# working.net
KiCad netlist of a schematic drawn in EAGLE
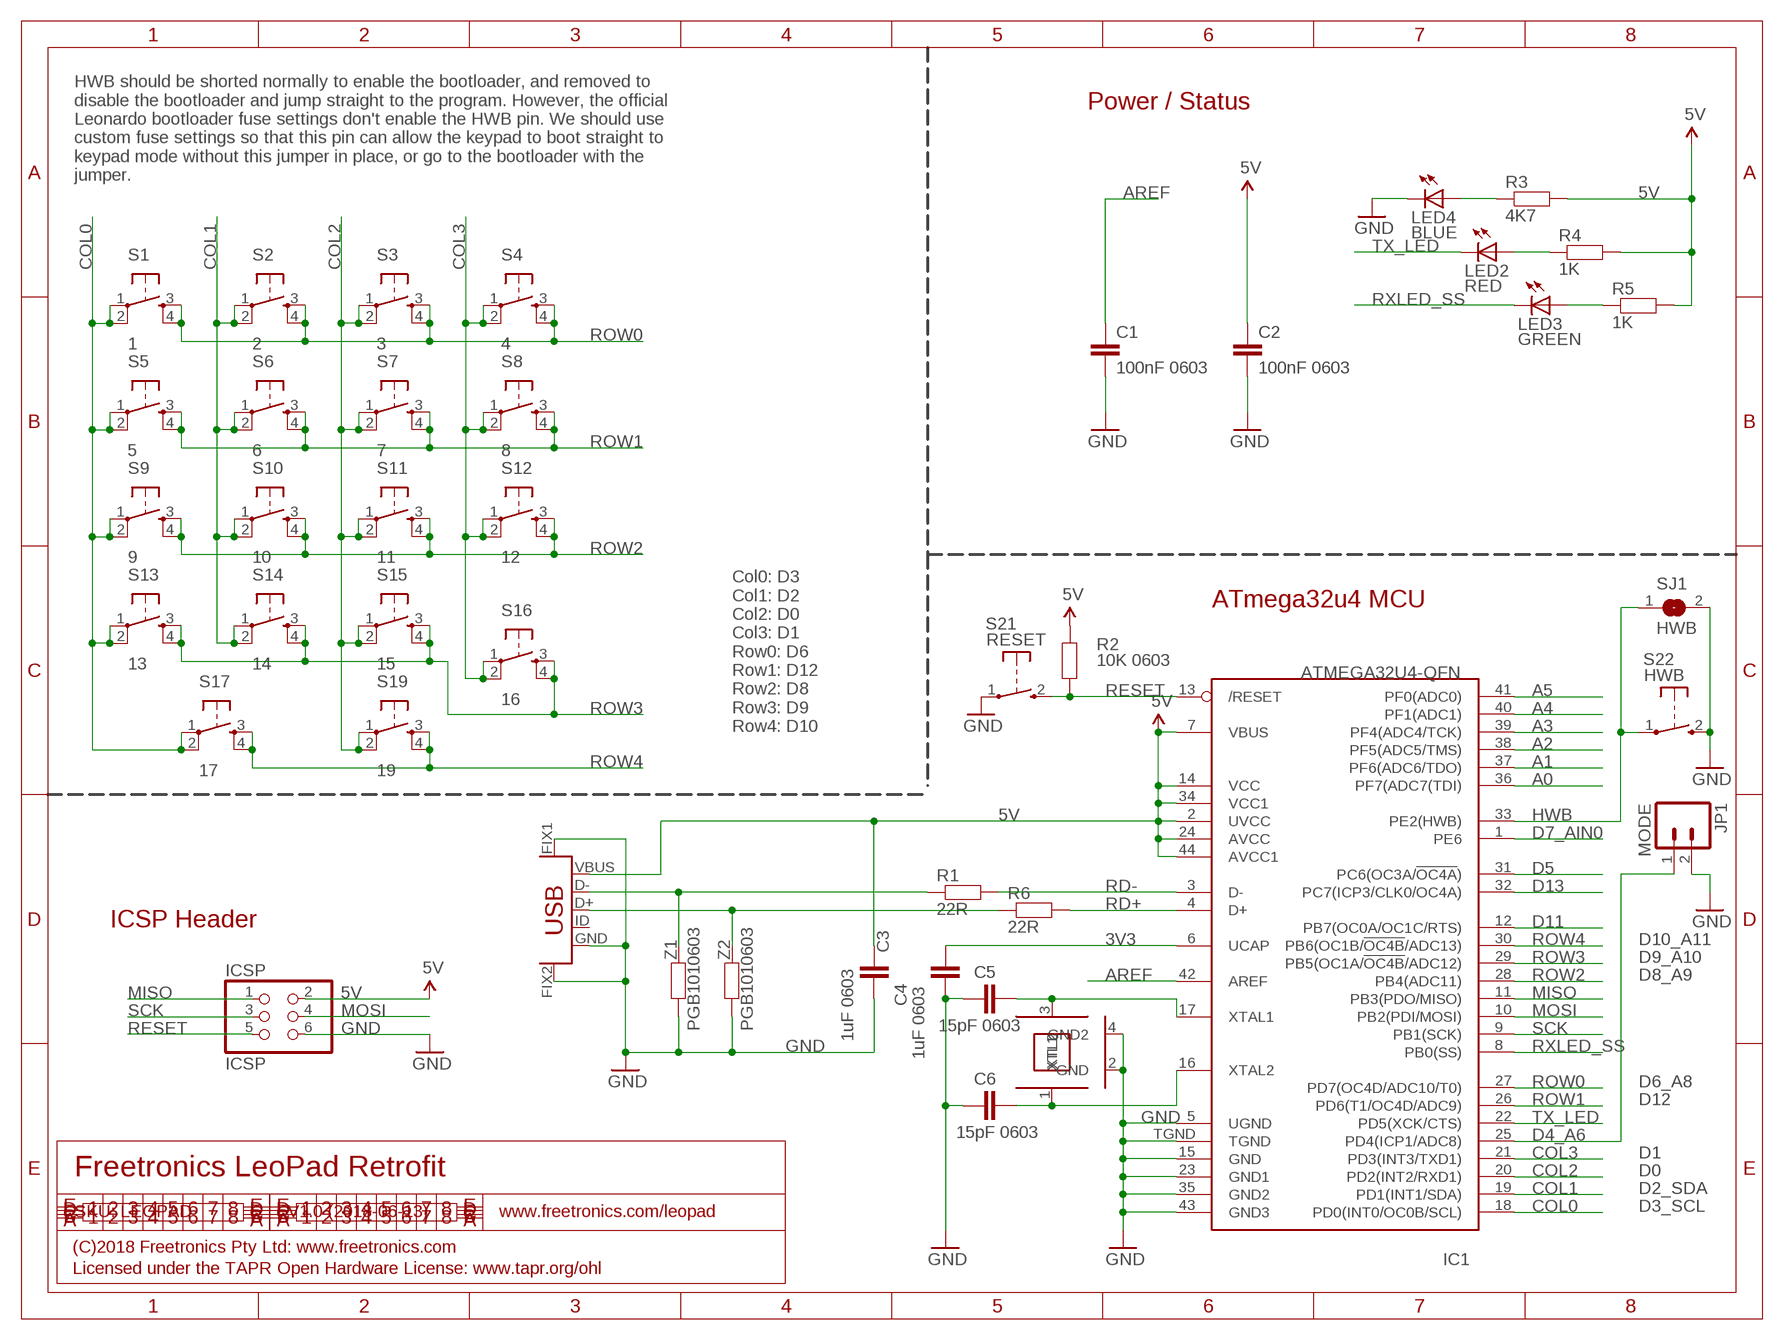
[diagram p0: schematic, sheet 1]

(export (version "E")
  (design (tool "Eeschema 10.0.6"))
  (components
    (comp (ref "C1")
      (value "100nF 0603")
      (footprint "eagle-import:0603")
      (libsource (lib "eagle-import") (part "CAP0603"))
    )
    (comp (ref "C2")
      (value "100nF 0603")
      (footprint "eagle-import:0603")
      (libsource (lib "eagle-import") (part "CAP0603"))
    )
    (comp (ref "C3")
      (value "1uF 0603")
      (footprint "eagle-import:0603")
      (libsource (lib "eagle-import") (part "CAP0603"))
    )
    (comp (ref "C4")
      (value "1uF 0603")
      (footprint "eagle-import:0603")
      (libsource (lib "eagle-import") (part "CAP0603"))
    )
    (comp (ref "C5")
      (value "15pF 0603")
      (footprint "eagle-import:0603")
      (libsource (lib "eagle-import") (part "CAP0603"))
    )
    (comp (ref "C6")
      (value "15pF 0603")
      (footprint "eagle-import:0603")
      (libsource (lib "eagle-import") (part "CAP0603"))
    )
    (comp (ref "IC1")
      (value "ATMEGA32U4-QFN")
      (footprint "eagle-import:QFN-44N")
      (libsource (lib "eagle-import") (part "ATMEGA32U4-QFN"))
    )
    (comp (ref "ICSP")
      (value "ICSP")
      (footprint "eagle-import:2X03")
      (libsource (lib "eagle-import") (part "PINHD-2X3"))
    )
    (comp (ref "JP1")
      (value "MODE")
      (footprint "eagle-import:1X02")
      (libsource (lib "eagle-import") (part "M02PTH"))
    )
    (comp (ref "LED2")
      (value "RED")
      (footprint "eagle-import:LED-0603")
      (libsource (lib "eagle-import") (part "LED0603"))
    )
    (comp (ref "LED3")
      (value "GREEN")
      (footprint "eagle-import:LED-0603")
      (libsource (lib "eagle-import") (part "LED0603"))
    )
    (comp (ref "LED4")
      (value "BLUE")
      (footprint "eagle-import:LED3MM")
      (libsource (lib "eagle-import") (part "LED3MM"))
    )
    (comp (ref "R1")
      (value "22R")
      (footprint "eagle-import:0603")
      (libsource (lib "eagle-import") (part "RESISTOR0603"))
    )
    (comp (ref "R2")
      (value "10K 0603")
      (footprint "eagle-import:0603")
      (libsource (lib "eagle-import") (part "freetronics-master-v1.1_RESISTOR0603"))
    )
    (comp (ref "R3")
      (value "4K7")
      (footprint "eagle-import:0603")
      (libsource (lib "eagle-import") (part "RESISTOR0603"))
    )
    (comp (ref "R4")
      (value "1K")
      (footprint "eagle-import:0603")
      (libsource (lib "eagle-import") (part "RESISTOR0603"))
    )
    (comp (ref "R5")
      (value "1K")
      (footprint "eagle-import:0603")
      (libsource (lib "eagle-import") (part "RESISTOR0603"))
    )
    (comp (ref "R6")
      (value "22R")
      (footprint "eagle-import:0603")
      (libsource (lib "eagle-import") (part "RESISTOR0603"))
    )
    (comp (ref "S1")
      (value "1")
      (footprint "eagle-import:TACTILE_SWITCH_SMD")
      (libsource (lib "eagle-import") (part "TAC_SWITCHSMD"))
    )
    (comp (ref "S2")
      (value "2")
      (footprint "eagle-import:TACTILE_SWITCH_SMD")
      (libsource (lib "eagle-import") (part "TAC_SWITCHSMD"))
    )
    (comp (ref "S3")
      (value "3")
      (footprint "eagle-import:TACTILE_SWITCH_SMD")
      (libsource (lib "eagle-import") (part "TAC_SWITCHSMD"))
    )
    (comp (ref "S4")
      (value "4")
      (footprint "eagle-import:TACTILE_SWITCH_SMD")
      (libsource (lib "eagle-import") (part "TAC_SWITCHSMD"))
    )
    (comp (ref "S5")
      (value "5")
      (footprint "eagle-import:TACTILE_SWITCH_SMD")
      (libsource (lib "eagle-import") (part "TAC_SWITCHSMD"))
    )
    (comp (ref "S6")
      (value "6")
      (footprint "eagle-import:TACTILE_SWITCH_SMD")
      (libsource (lib "eagle-import") (part "TAC_SWITCHSMD"))
    )
    (comp (ref "S7")
      (value "7")
      (footprint "eagle-import:TACTILE_SWITCH_SMD")
      (libsource (lib "eagle-import") (part "TAC_SWITCHSMD"))
    )
    (comp (ref "S8")
      (value "8")
      (footprint "eagle-import:TACTILE_SWITCH_SMD")
      (libsource (lib "eagle-import") (part "TAC_SWITCHSMD"))
    )
    (comp (ref "S9")
      (value "9")
      (footprint "eagle-import:TACTILE_SWITCH_SMD")
      (libsource (lib "eagle-import") (part "TAC_SWITCHSMD"))
    )
    (comp (ref "S10")
      (value "10")
      (footprint "eagle-import:TACTILE_SWITCH_SMD")
      (libsource (lib "eagle-import") (part "TAC_SWITCHSMD"))
    )
    (comp (ref "S11")
      (value "11")
      (footprint "eagle-import:TACTILE_SWITCH_SMD")
      (libsource (lib "eagle-import") (part "TAC_SWITCHSMD"))
    )
    (comp (ref "S12")
      (value "12")
      (footprint "eagle-import:TACTILE_SWITCH_SMD")
      (libsource (lib "eagle-import") (part "TAC_SWITCHSMD"))
    )
    (comp (ref "S13")
      (value "13")
      (footprint "eagle-import:TACTILE_SWITCH_SMD")
      (libsource (lib "eagle-import") (part "TAC_SWITCHSMD"))
    )
    (comp (ref "S14")
      (value "14")
      (footprint "eagle-import:TACTILE_SWITCH_SMD")
      (libsource (lib "eagle-import") (part "TAC_SWITCHSMD"))
    )
    (comp (ref "S15")
      (value "15")
      (footprint "eagle-import:TACTILE_SWITCH_SMD")
      (libsource (lib "eagle-import") (part "TAC_SWITCHSMD"))
    )
    (comp (ref "S16")
      (value "16")
      (footprint "eagle-import:TACTILE_SWITCH_SMD")
      (libsource (lib "eagle-import") (part "TAC_SWITCHSMD"))
    )
    (comp (ref "S17")
      (value "17")
      (footprint "eagle-import:TACTILE_SWITCH_SMD")
      (libsource (lib "eagle-import") (part "TAC_SWITCHSMD"))
    )
    (comp (ref "S19")
      (value "19")
      (footprint "eagle-import:TACTILE_SWITCH_SMD")
      (libsource (lib "eagle-import") (part "TAC_SWITCHSMD"))
    )
    (comp (ref "S21")
      (value "RESET")
      (footprint "eagle-import:TACTILE_SWITCH_SMD_2PIN_TINY")
      (libsource (lib "eagle-import") (part "TAC_SWITCH_2PINSMT"))
    )
    (comp (ref "S22")
      (value "HWB")
      (footprint "eagle-import:TACTILE_SWITCH_SMD_2PIN_TINY")
      (libsource (lib "eagle-import") (part "TAC_SWITCH_2PINSMT"))
    )
    (comp (ref "SJ1")
      (value "HWB")
      (footprint "eagle-import:SJ")
      (libsource (lib "eagle-import") (part "SJN"))
    )
    (comp (ref "U$2")
      (value "USB-2P2P")
      (footprint "eagle-import:USB-MICROB-MB05PMXX")
      (libsource (lib "eagle-import") (part "USB-2P2P"))
    )
    (comp (ref "XTL1")
      (value "16MHz")
      (footprint "eagle-import:CRYSTAL-SMD-3X2")
      (libsource (lib "eagle-import") (part "CRYSTAL-GND3X2"))
    )
    (comp (ref "Z1")
      (value "PGB1010603")
      (footprint "eagle-import:0603")
      (libsource (lib "eagle-import") (part "freetronics-master-v1.1_RESISTOR0603"))
    )
    (comp (ref "Z2")
      (value "PGB1010603")
      (footprint "eagle-import:0603")
      (libsource (lib "eagle-import") (part "freetronics-master-v1.1_RESISTOR0603"))
    )
  )
  (nets
    (net (code "1") (name "/3V3") (class "Default")
      (node (ref "C4") (pin "2") (pinfunction "2_2") (pintype "passive"))
      (node (ref "IC1") (pin "6") (pinfunction "UCAP_6") (pintype "bidirectional"))
    )
    (net (code "2") (name "/A0") (class "Default")
      (node (ref "IC1") (pin "36") (pinfunction "PF7(ADC7(TDI)_36") (pintype "bidirectional"))
    )
    (net (code "3") (name "/A1") (class "Default")
      (node (ref "IC1") (pin "37") (pinfunction "PF6(ADC6/TDO)_37") (pintype "bidirectional"))
    )
    (net (code "4") (name "/A2") (class "Default")
      (node (ref "IC1") (pin "38") (pinfunction "PF5(ADC5/TMS)_38") (pintype "bidirectional"))
    )
    (net (code "5") (name "/A3") (class "Default")
      (node (ref "IC1") (pin "39") (pinfunction "PF4(ADC4/TCK)_39") (pintype "bidirectional"))
    )
    (net (code "6") (name "/A4") (class "Default")
      (node (ref "IC1") (pin "40") (pinfunction "PF1(ADC1)_40") (pintype "bidirectional"))
    )
    (net (code "7") (name "/A5") (class "Default")
      (node (ref "IC1") (pin "41") (pinfunction "PF0(ADC0)_41") (pintype "bidirectional"))
    )
    (net (code "8") (name "/AREF") (class "Default")
      (node (ref "C1") (pin "1") (pinfunction "1_1") (pintype "passive"))
      (node (ref "IC1") (pin "42") (pinfunction "AREF_42") (pintype "bidirectional"))
    )
    (net (code "9") (name "/COL0") (class "Default")
      (node (ref "IC1") (pin "18") (pinfunction "PD0(INT0/OC0B/SCL)_18") (pintype "bidirectional"))
      (node (ref "S1") (pin "1") (pinfunction "1_1") (pintype "passive"))
      (node (ref "S1") (pin "2") (pinfunction "2_2") (pintype "passive"))
      (node (ref "S13") (pin "1") (pinfunction "1_1") (pintype "passive"))
      (node (ref "S13") (pin "2") (pinfunction "2_2") (pintype "passive"))
      (node (ref "S17") (pin "1") (pinfunction "1_1") (pintype "passive"))
      (node (ref "S17") (pin "2") (pinfunction "2_2") (pintype "passive"))
      (node (ref "S5") (pin "1") (pinfunction "1_1") (pintype "passive"))
      (node (ref "S5") (pin "2") (pinfunction "2_2") (pintype "passive"))
      (node (ref "S9") (pin "1") (pinfunction "1_1") (pintype "passive"))
      (node (ref "S9") (pin "2") (pinfunction "2_2") (pintype "passive"))
    )
    (net (code "10") (name "/COL1") (class "Default")
      (node (ref "IC1") (pin "19") (pinfunction "PD1(INT1/SDA)_19") (pintype "bidirectional"))
      (node (ref "S10") (pin "1") (pinfunction "1_1") (pintype "passive"))
      (node (ref "S10") (pin "2") (pinfunction "2_2") (pintype "passive"))
      (node (ref "S14") (pin "1") (pinfunction "1_1") (pintype "passive"))
      (node (ref "S14") (pin "2") (pinfunction "2_2") (pintype "passive"))
      (node (ref "S2") (pin "1") (pinfunction "1_1") (pintype "passive"))
      (node (ref "S2") (pin "2") (pinfunction "2_2") (pintype "passive"))
      (node (ref "S6") (pin "1") (pinfunction "1_1") (pintype "passive"))
      (node (ref "S6") (pin "2") (pinfunction "2_2") (pintype "passive"))
    )
    (net (code "11") (name "/COL2") (class "Default")
      (node (ref "IC1") (pin "20") (pinfunction "PD2(INT2/RXD1)_20") (pintype "bidirectional"))
      (node (ref "S11") (pin "1") (pinfunction "1_1") (pintype "passive"))
      (node (ref "S11") (pin "2") (pinfunction "2_2") (pintype "passive"))
      (node (ref "S15") (pin "1") (pinfunction "1_1") (pintype "passive"))
      (node (ref "S15") (pin "2") (pinfunction "2_2") (pintype "passive"))
      (node (ref "S19") (pin "1") (pinfunction "1_1") (pintype "passive"))
      (node (ref "S19") (pin "2") (pinfunction "2_2") (pintype "passive"))
      (node (ref "S3") (pin "1") (pinfunction "1_1") (pintype "passive"))
      (node (ref "S3") (pin "2") (pinfunction "2_2") (pintype "passive"))
      (node (ref "S7") (pin "1") (pinfunction "1_1") (pintype "passive"))
      (node (ref "S7") (pin "2") (pinfunction "2_2") (pintype "passive"))
    )
    (net (code "12") (name "/COL3") (class "Default")
      (node (ref "IC1") (pin "21") (pinfunction "PD3(INT3/TXD1)_21") (pintype "bidirectional"))
      (node (ref "S12") (pin "1") (pinfunction "1_1") (pintype "passive"))
      (node (ref "S12") (pin "2") (pinfunction "2_2") (pintype "passive"))
      (node (ref "S16") (pin "1") (pinfunction "1_1") (pintype "passive"))
      (node (ref "S16") (pin "2") (pinfunction "2_2") (pintype "passive"))
      (node (ref "S4") (pin "1") (pinfunction "1_1") (pintype "passive"))
      (node (ref "S4") (pin "2") (pinfunction "2_2") (pintype "passive"))
      (node (ref "S8") (pin "1") (pinfunction "1_1") (pintype "passive"))
      (node (ref "S8") (pin "2") (pinfunction "2_2") (pintype "passive"))
    )
    (net (code "13") (name "/D4_A6") (class "Default")
      (node (ref "IC1") (pin "25") (pinfunction "PD4(ICP1/ADC8)_25") (pintype "bidirectional"))
      (node (ref "JP1") (pin "1") (pinfunction "1_1") (pintype "passive"))
    )
    (net (code "14") (name "/D5") (class "Default")
      (node (ref "IC1") (pin "31") (pinfunction "PC6(OC3A/~{OC4A})_31") (pintype "bidirectional"))
    )
    (net (code "15") (name "/D7_AIN0") (class "Default")
      (node (ref "IC1") (pin "1") (pinfunction "PE6_1") (pintype "bidirectional"))
    )
    (net (code "16") (name "/D11") (class "Default")
      (node (ref "IC1") (pin "12") (pinfunction "PB7(OC0A/OC1C/RTS)_12") (pintype "bidirectional"))
    )
    (net (code "17") (name "/D13") (class "Default")
      (node (ref "IC1") (pin "32") (pinfunction "PC7(ICP3/CLK0/OC4A)_32") (pintype "bidirectional"))
    )
    (net (code "18") (name "/HWB") (class "Default")
      (node (ref "IC1") (pin "33") (pinfunction "PE2(HWB)_33") (pintype "bidirectional"))
      (node (ref "S22") (pin "1") (pinfunction "P_1") (pintype "passive"))
      (node (ref "SJ1") (pin "1") (pinfunction "1_1") (pintype "passive"))
    )
    (net (code "19") (name "/MISO") (class "Default")
      (node (ref "IC1") (pin "11") (pinfunction "PB3(PDO/MISO)_11") (pintype "bidirectional"))
      (node (ref "ICSP") (pin "1") (pinfunction "1_1") (pintype "passive"))
    )
    (net (code "20") (name "/MOSI") (class "Default")
      (node (ref "IC1") (pin "10") (pinfunction "PB2(PDI/MOSI)_10") (pintype "bidirectional"))
      (node (ref "ICSP") (pin "4") (pinfunction "4_4") (pintype "passive"))
    )
    (net (code "21") (name "/RD+") (class "Default")
      (node (ref "IC1") (pin "4") (pinfunction "D+_4") (pintype "bidirectional"))
      (node (ref "R6") (pin "2") (pinfunction "2_2") (pintype "passive"))
    )
    (net (code "22") (name "/RD-") (class "Default")
      (node (ref "IC1") (pin "3") (pinfunction "D-_3") (pintype "bidirectional"))
      (node (ref "R1") (pin "2") (pinfunction "2_2") (pintype "passive"))
    )
    (net (code "23") (name "/RESET") (class "Default")
      (node (ref "IC1") (pin "13") (pinfunction "/RESET_13") (pintype "bidirectional"))
      (node (ref "ICSP") (pin "5") (pinfunction "5_5") (pintype "passive"))
      (node (ref "R2") (pin "1") (pinfunction "1_1") (pintype "passive"))
      (node (ref "S21") (pin "2") (pinfunction "S_2") (pintype "passive"))
    )
    (net (code "24") (name "/ROW0") (class "Default")
      (node (ref "IC1") (pin "27") (pinfunction "PD7(OC4D/ADC10/T0)_27") (pintype "bidirectional"))
      (node (ref "S1") (pin "3") (pinfunction "3_3") (pintype "passive"))
      (node (ref "S1") (pin "4") (pinfunction "4_4") (pintype "passive"))
      (node (ref "S2") (pin "3") (pinfunction "3_3") (pintype "passive"))
      (node (ref "S2") (pin "4") (pinfunction "4_4") (pintype "passive"))
      (node (ref "S3") (pin "3") (pinfunction "3_3") (pintype "passive"))
      (node (ref "S3") (pin "4") (pinfunction "4_4") (pintype "passive"))
      (node (ref "S4") (pin "3") (pinfunction "3_3") (pintype "passive"))
      (node (ref "S4") (pin "4") (pinfunction "4_4") (pintype "passive"))
    )
    (net (code "25") (name "/ROW1") (class "Default")
      (node (ref "IC1") (pin "26") (pinfunction "PD6(T1/OC4D/ADC9)_26") (pintype "bidirectional"))
      (node (ref "S5") (pin "3") (pinfunction "3_3") (pintype "passive"))
      (node (ref "S5") (pin "4") (pinfunction "4_4") (pintype "passive"))
      (node (ref "S6") (pin "3") (pinfunction "3_3") (pintype "passive"))
      (node (ref "S6") (pin "4") (pinfunction "4_4") (pintype "passive"))
      (node (ref "S7") (pin "3") (pinfunction "3_3") (pintype "passive"))
      (node (ref "S7") (pin "4") (pinfunction "4_4") (pintype "passive"))
      (node (ref "S8") (pin "3") (pinfunction "3_3") (pintype "passive"))
      (node (ref "S8") (pin "4") (pinfunction "4_4") (pintype "passive"))
    )
    (net (code "26") (name "/ROW2") (class "Default")
      (node (ref "IC1") (pin "28") (pinfunction "PB4(ADC11)_28") (pintype "bidirectional"))
      (node (ref "S10") (pin "3") (pinfunction "3_3") (pintype "passive"))
      (node (ref "S10") (pin "4") (pinfunction "4_4") (pintype "passive"))
      (node (ref "S11") (pin "3") (pinfunction "3_3") (pintype "passive"))
      (node (ref "S11") (pin "4") (pinfunction "4_4") (pintype "passive"))
      (node (ref "S12") (pin "3") (pinfunction "3_3") (pintype "passive"))
      (node (ref "S12") (pin "4") (pinfunction "4_4") (pintype "passive"))
      (node (ref "S9") (pin "3") (pinfunction "3_3") (pintype "passive"))
      (node (ref "S9") (pin "4") (pinfunction "4_4") (pintype "passive"))
    )
    (net (code "27") (name "/ROW3") (class "Default")
      (node (ref "IC1") (pin "29") (pinfunction "PB5(OC1A/~{OC4B}/ADC12)_29") (pintype "bidirectional"))
      (node (ref "S13") (pin "3") (pinfunction "3_3") (pintype "passive"))
      (node (ref "S13") (pin "4") (pinfunction "4_4") (pintype "passive"))
      (node (ref "S14") (pin "3") (pinfunction "3_3") (pintype "passive"))
      (node (ref "S14") (pin "4") (pinfunction "4_4") (pintype "passive"))
      (node (ref "S15") (pin "3") (pinfunction "3_3") (pintype "passive"))
      (node (ref "S15") (pin "4") (pinfunction "4_4") (pintype "passive"))
      (node (ref "S16") (pin "3") (pinfunction "3_3") (pintype "passive"))
      (node (ref "S16") (pin "4") (pinfunction "4_4") (pintype "passive"))
    )
    (net (code "28") (name "/ROW4") (class "Default")
      (node (ref "IC1") (pin "30") (pinfunction "PB6(OC1B/~{OC4B}/ADC13)_30") (pintype "bidirectional"))
      (node (ref "S17") (pin "3") (pinfunction "3_3") (pintype "passive"))
      (node (ref "S17") (pin "4") (pinfunction "4_4") (pintype "passive"))
      (node (ref "S19") (pin "3") (pinfunction "3_3") (pintype "passive"))
      (node (ref "S19") (pin "4") (pinfunction "4_4") (pintype "passive"))
    )
    (net (code "29") (name "/RXLED_SS") (class "Default")
      (node (ref "IC1") (pin "8") (pinfunction "PB0(SS)_8") (pintype "bidirectional"))
      (node (ref "LED3") (pin "C") (pinfunction "C_C") (pintype "passive"))
    )
    (net (code "30") (name "/SCK") (class "Default")
      (node (ref "IC1") (pin "9") (pinfunction "PB1(SCK)_9") (pintype "bidirectional"))
      (node (ref "ICSP") (pin "3") (pinfunction "3_3") (pintype "passive"))
    )
    (net (code "31") (name "/TX_LED") (class "Default")
      (node (ref "IC1") (pin "22") (pinfunction "PD5(XCK/CTS)_22") (pintype "bidirectional"))
      (node (ref "LED2") (pin "C") (pinfunction "C_C") (pintype "passive"))
    )
    (net (code "32") (name "5V") (class "Default")
      (node (ref "C2") (pin "1") (pinfunction "1_1") (pintype "passive"))
      (node (ref "C3") (pin "1") (pinfunction "1_1") (pintype "passive"))
      (node (ref "IC1") (pin "14") (pinfunction "VCC_14") (pintype "bidirectional"))
      (node (ref "IC1") (pin "2") (pinfunction "UVCC_2") (pintype "bidirectional"))
      (node (ref "IC1") (pin "24") (pinfunction "AVCC_24") (pintype "bidirectional"))
      (node (ref "IC1") (pin "34") (pinfunction "VCC1_34") (pintype "bidirectional"))
      (node (ref "IC1") (pin "44") (pinfunction "AVCC1_44") (pintype "bidirectional"))
      (node (ref "IC1") (pin "7") (pinfunction "VBUS_7") (pintype "bidirectional"))
      (node (ref "ICSP") (pin "2") (pinfunction "2_2") (pintype "passive"))
      (node (ref "R2") (pin "2") (pinfunction "2_2") (pintype "passive"))
      (node (ref "R3") (pin "2") (pinfunction "2_2") (pintype "passive"))
      (node (ref "R4") (pin "2") (pinfunction "2_2") (pintype "passive"))
      (node (ref "R5") (pin "2") (pinfunction "2_2") (pintype "passive"))
      (node (ref "U$2") (pin "VBUS") (pinfunction "VBUS_VBUS") (pintype "bidirectional"))
    )
    (net (code "33") (name "GND") (class "Default")
      (node (ref "C1") (pin "2") (pinfunction "2_2") (pintype "passive"))
      (node (ref "C2") (pin "2") (pinfunction "2_2") (pintype "passive"))
      (node (ref "C3") (pin "2") (pinfunction "2_2") (pintype "passive"))
      (node (ref "C4") (pin "1") (pinfunction "1_1") (pintype "passive"))
      (node (ref "C5") (pin "1") (pinfunction "1_1") (pintype "passive"))
      (node (ref "C6") (pin "1") (pinfunction "1_1") (pintype "passive"))
      (node (ref "IC1") (pin "15") (pinfunction "GND_15") (pintype "bidirectional"))
      (node (ref "IC1") (pin "23") (pinfunction "GND1_23") (pintype "bidirectional"))
      (node (ref "IC1") (pin "35") (pinfunction "GND2_35") (pintype "bidirectional"))
      (node (ref "IC1") (pin "43") (pinfunction "GND3_43") (pintype "bidirectional"))
      (node (ref "IC1") (pin "5") (pinfunction "UGND_5") (pintype "bidirectional"))
      (node (ref "IC1") (pin "TGND") (pinfunction "TGND_TGND") (pintype "bidirectional"))
      (node (ref "ICSP") (pin "6") (pinfunction "6_6") (pintype "passive"))
      (node (ref "JP1") (pin "2") (pinfunction "2_2") (pintype "passive"))
      (node (ref "LED4") (pin "K") (pinfunction "C_K") (pintype "passive"))
      (node (ref "S21") (pin "1") (pinfunction "P_1") (pintype "passive"))
      (node (ref "S22") (pin "2") (pinfunction "S_2") (pintype "passive"))
      (node (ref "SJ1") (pin "2") (pinfunction "2_2") (pintype "passive"))
      (node (ref "U$2") (pin "FIX1") (pinfunction "TAB1_FIX1") (pintype "bidirectional"))
      (node (ref "U$2") (pin "FIX2") (pinfunction "TAB2_FIX2") (pintype "bidirectional"))
      (node (ref "U$2") (pin "GND") (pinfunction "GND_GND") (pintype "bidirectional"))
      (node (ref "XTL1") (pin "2") (pinfunction "GND_2") (pintype "bidirectional"))
      (node (ref "XTL1") (pin "4") (pinfunction "GND2_4") (pintype "bidirectional"))
      (node (ref "Z1") (pin "1") (pinfunction "1_1") (pintype "passive"))
      (node (ref "Z2") (pin "1") (pinfunction "1_1") (pintype "passive"))
    )
    (net (code "34") (name "Net-(IC1-XTAL1)") (class "Default")
      (node (ref "C5") (pin "2") (pinfunction "2_2") (pintype "passive"))
      (node (ref "IC1") (pin "17") (pinfunction "XTAL1_17") (pintype "bidirectional"))
      (node (ref "XTL1") (pin "3") (pinfunction "XTL2_3") (pintype "bidirectional"))
    )
    (net (code "35") (name "Net-(IC1-XTAL2)") (class "Default")
      (node (ref "C6") (pin "2") (pinfunction "2_2") (pintype "passive"))
      (node (ref "IC1") (pin "16") (pinfunction "XTAL2_16") (pintype "bidirectional"))
      (node (ref "XTL1") (pin "1") (pinfunction "XTL1_1") (pintype "bidirectional"))
    )
    (net (code "36") (name "Net-(LED2-PadA)") (class "Default")
      (node (ref "LED2") (pin "A") (pinfunction "A_A") (pintype "passive"))
      (node (ref "R4") (pin "1") (pinfunction "1_1") (pintype "passive"))
    )
    (net (code "37") (name "Net-(LED3-PadA)") (class "Default")
      (node (ref "LED3") (pin "A") (pinfunction "A_A") (pintype "passive"))
      (node (ref "R5") (pin "1") (pinfunction "1_1") (pintype "passive"))
    )
    (net (code "38") (name "Net-(LED4-PadA)") (class "Default")
      (node (ref "LED4") (pin "A") (pinfunction "A_A") (pintype "passive"))
      (node (ref "R3") (pin "1") (pinfunction "1_1") (pintype "passive"))
    )
    (net (code "39") (name "Net-(R1-Pad1)") (class "Default")
      (node (ref "R1") (pin "1") (pinfunction "1_1") (pintype "passive"))
      (node (ref "U$2") (pin "D-") (pinfunction "D-_D-") (pintype "bidirectional"))
      (node (ref "Z1") (pin "2") (pinfunction "2_2") (pintype "passive"))
    )
    (net (code "40") (name "Net-(R6-Pad1)") (class "Default")
      (node (ref "R6") (pin "1") (pinfunction "1_1") (pintype "passive"))
      (node (ref "U$2") (pin "D+") (pinfunction "D+_D+") (pintype "bidirectional"))
      (node (ref "Z2") (pin "2") (pinfunction "2_2") (pintype "passive"))
    )
    (net (code "41") (name "unconnected-(U$2-PadID)") (class "Default")
      (node (ref "U$2") (pin "ID") (pinfunction "ID_ID") (pintype "bidirectional"))
    )
  )
)
